# Barrido_1fuente.net
KiCad netlist of a schematic drawn in Altium Designer
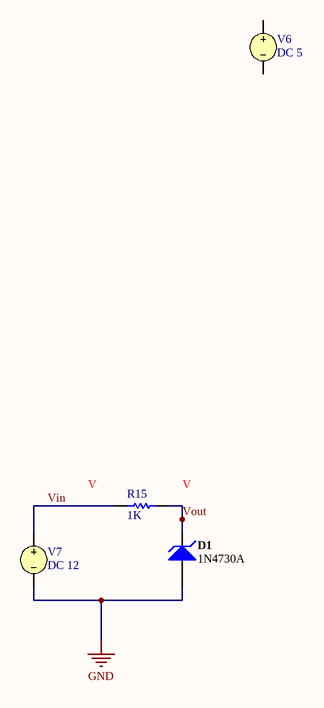
[diagram p0: Barrido_1fuente.SchDoc]

(export (version "E")
  (design (tool "Eeschema 10.0.6"))
  (components
    (comp (ref "D1")
      (value "1N4730A")
      (footprint "FAIR-DO-41-2_V")
      (description "Zener Diode, 3.9V, 1W, 5%, -65 to 200 degC, 2-Pin DO-41, Body 2.72 x 5.2 mm, RoHS")
      (fields (field (name "TOLERANCE") "5%") (field (name "MANUFACTURER") "Fairchild Semiconductor"))
      (libsource (lib "Altium Content Vault") (part "FAIR-DZEN-A1K2-2"))
    )
    (comp (ref "R15")
      (value "1K")
      (description "Resistor")
      (libsource (lib "Simulation Generic Components") (part "Resistor"))
    )
    (comp (ref "V6")
      (value "DC 5")
      (description "Voltage Source")
      (fields (field (name "PUBLISHER") "Altium Limited"))
      (libsource (lib "Simulation Generic Components") (part "VSRC"))
    )
    (comp (ref "V7")
      (value "DC 12")
      (description "Voltage Source")
      (fields (field (name "PUBLISHER") "Altium Limited"))
      (libsource (lib "Simulation Generic Components") (part "VSRC"))
    )
  )
  (nets
    (net (code "1") (name "/Vin") (class "Default")
      (node (ref "R15") (pin "1") (pinfunction "1_1") (pintype "passive"))
      (node (ref "V7") (pin "1") (pinfunction "1_1") (pintype "passive"))
    )
    (net (code "2") (name "/Vout") (class "Default")
      (node (ref "D1") (pin "2") (pinfunction "K_2") (pintype "passive"))
      (node (ref "R15") (pin "2") (pinfunction "2_2") (pintype "passive"))
    )
    (net (code "3") (name "GND") (class "Default")
      (node (ref "D1") (pin "1") (pinfunction "A_1") (pintype "passive"))
      (node (ref "V7") (pin "2") (pinfunction "2_2") (pintype "passive"))
    )
    (net (code "4") (name "unconnected-(V6-Pad1)") (class "Default")
      (node (ref "V6") (pin "1") (pinfunction "1_1") (pintype "passive"))
    )
    (net (code "5") (name "unconnected-(V6-Pad2)") (class "Default")
      (node (ref "V6") (pin "2") (pinfunction "2_2") (pintype "passive"))
    )
  )
)
